# DIY_OpenEVSE_PLUS.net
KiCad netlist of a schematic drawn in EAGLE
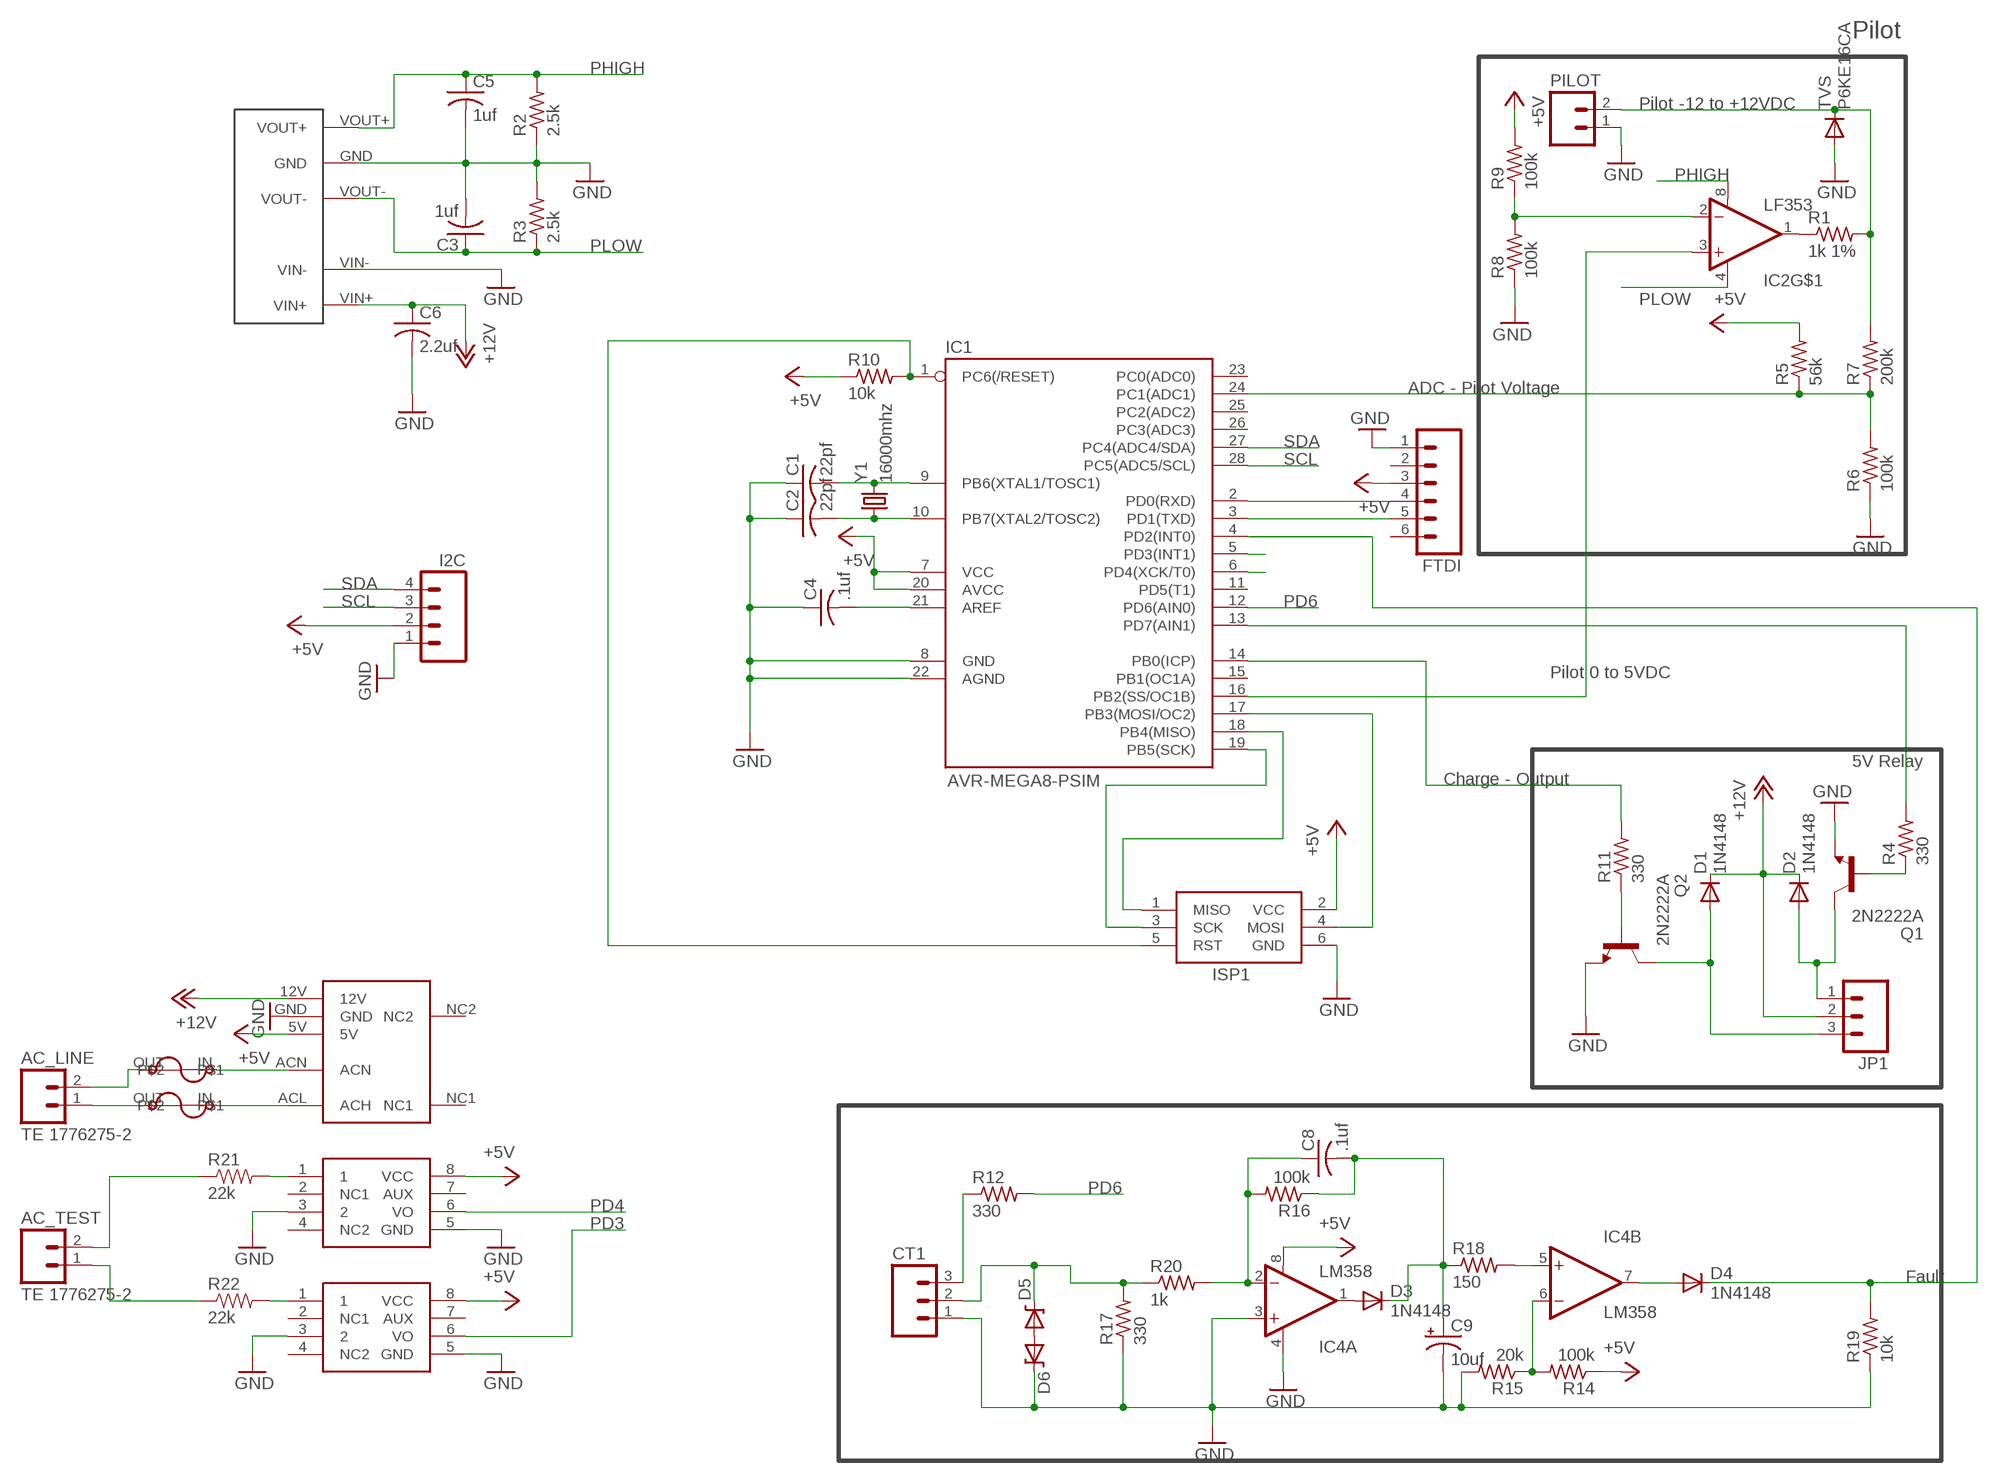
[diagram p0: schematic, sheet 1]

(export (version "E")
  (design (tool "Eeschema 10.0.6"))
  (components
    (comp (ref "AC_LINE")
      (value "TE 1776275-2")
      (footprint "eagle-import:SCREWTERMINAL-3.5MM-2_LOCK")
      (libsource (lib "eagle-import") (part "M023.5MM_LOCK"))
    )
    (comp (ref "AC_TEST")
      (value "TE 1776275-2")
      (footprint "eagle-import:SCREWTERMINAL-3.5MM-2_LOCK")
      (libsource (lib "eagle-import") (part "M023.5MM_LOCK"))
    )
    (comp (ref "C1")
      (value "22pf")
      (footprint "eagle-import:C025-024X044")
      (libsource (lib "eagle-import") (part "C-US025-024X044"))
    )
    (comp (ref "C2")
      (value "22pf")
      (footprint "eagle-import:C025-024X044")
      (libsource (lib "eagle-import") (part "C-US025-024X044"))
    )
    (comp (ref "C3")
      (value "1uf")
      (footprint "eagle-import:C025-024X044")
      (libsource (lib "eagle-import") (part "C-US025-024X044"))
    )
    (comp (ref "C4")
      (value ".1uf")
      (footprint "eagle-import:C025-024X044")
      (libsource (lib "eagle-import") (part "C-US025-024X044"))
    )
    (comp (ref "C5")
      (value "1uf")
      (footprint "eagle-import:C025-024X044")
      (libsource (lib "eagle-import") (part "C-US025-024X044"))
    )
    (comp (ref "C6")
      (value "2.2uf")
      (footprint "eagle-import:C025-024X044")
      (libsource (lib "eagle-import") (part "C-US025-024X044"))
    )
    (comp (ref "C8")
      (value ".1uf")
      (footprint "eagle-import:C025-024X044")
      (libsource (lib "eagle-import") (part "C-US025-024X044"))
    )
    (comp (ref "C9")
      (value "10uf")
      (footprint "eagle-import:CPOL-RADIAL-10UF-25V")
      (libsource (lib "eagle-import") (part "CAP_POLPTH2"))
    )
    (comp (ref "CT1")
      (value "M03LOCK")
      (footprint "eagle-import:1X03_LOCK")
      (libsource (lib "eagle-import") (part "M03LOCK"))
    )
    (comp (ref "D1")
      (value "1N4148")
      (footprint "eagle-import:DIODE-1N4148")
      (libsource (lib "eagle-import") (part "DIODE1N4148"))
    )
    (comp (ref "D2")
      (value "1N4148")
      (footprint "eagle-import:DIODE-1N4148")
      (libsource (lib "eagle-import") (part "DIODE1N4148"))
    )
    (comp (ref "D3")
      (value "1N4148")
      (footprint "eagle-import:DIODE-1N4148")
      (libsource (lib "eagle-import") (part "DIODE1N4148"))
    )
    (comp (ref "D4")
      (value "1N4148")
      (footprint "eagle-import:DIODE-1N4148")
      (libsource (lib "eagle-import") (part "DIODE1N4148"))
    )
    (comp (ref "D5")
      (value "DIODE-ZENERPTH")
      (footprint "eagle-import:DIODE-ZENER")
      (libsource (lib "eagle-import") (part "DIODE-ZENERPTH"))
    )
    (comp (ref "D6")
      (value "DIODE-ZENERPTH")
      (footprint "eagle-import:DIODE-ZENER")
      (libsource (lib "eagle-import") (part "DIODE-ZENERPTH"))
    )
    (comp (ref "DCDC")
      (value "D107E")
      (footprint "eagle-import:DCDC_SIP")
      (libsource (lib "eagle-import") (part "DCDC_SIP"))
    )
    (comp (ref "FTDI")
      (value "M06LOCK")
      (footprint "eagle-import:1X06_LOCK")
      (libsource (lib "eagle-import") (part "M06LOCK"))
    )
    (comp (ref "I2C")
      (value "M04LOCK")
      (footprint "eagle-import:1X04_LOCK")
      (libsource (lib "eagle-import") (part "M04LOCK"))
    )
    (comp (ref "IC1")
      (value "AVR-MEGA8-PSIM")
      (footprint "eagle-import:DIL28-3-SIMON")
      (libsource (lib "eagle-import") (part "AVR-MEGA8-PSIM"))
    )
    (comp (ref "IC2")
      (value "LF353")
      (footprint "eagle-import:DIP08")
      (libsource (lib "eagle-import") (part "LM358"))
    )
    (comp (ref "IC3")
      (value "MID400")
      (footprint "eagle-import:DIP08")
      (libsource (lib "eagle-import") (part "MID400"))
    )
    (comp (ref "IC4")
      (value "LM358")
      (footprint "eagle-import:DIP08")
      (libsource (lib "eagle-import") (part "OPAMP-DUALDIP"))
    )
    (comp (ref "IC5")
      (value "MID400")
      (footprint "eagle-import:DIP08")
      (libsource (lib "eagle-import") (part "MID400"))
    )
    (comp (ref "ISP1")
      (value "AVRISP-6")
      (footprint "eagle-import:AVRISP")
      (libsource (lib "eagle-import") (part "AVRISP-6"))
    )
    (comp (ref "JP1")
      (value "M03SCREW_LOCK")
      (footprint "eagle-import:SCREWTERMINAL-3.5MM-3_LOCK.007S")
      (libsource (lib "eagle-import") (part "M03SCREW_LOCK"))
    )
    (comp (ref "PILOT")
      (value "M025MM")
      (footprint "eagle-import:SCREWTERMINAL-5MM-2")
      (libsource (lib "eagle-import") (part "M025MM"))
    )
    (comp (ref "Q1")
      (value "2N2222A")
      (footprint "eagle-import:TO18")
      (libsource (lib "eagle-import") (part "2N2222A"))
    )
    (comp (ref "Q2")
      (value "2N2222A")
      (footprint "eagle-import:TO18")
      (libsource (lib "eagle-import") (part "2N2222A"))
    )
    (comp (ref "R1")
      (value "1k 1%")
      (footprint "eagle-import:0204_7")
      (libsource (lib "eagle-import") (part "R-US_0204/7"))
    )
    (comp (ref "R2")
      (value "2.5k")
      (footprint "eagle-import:0204_7")
      (libsource (lib "eagle-import") (part "R-US_0204/7"))
    )
    (comp (ref "R3")
      (value "2.5k")
      (footprint "eagle-import:0204_7")
      (libsource (lib "eagle-import") (part "R-US_0204/7"))
    )
    (comp (ref "R4")
      (value "330")
      (footprint "eagle-import:0204_7")
      (libsource (lib "eagle-import") (part "R-US_0204/7"))
    )
    (comp (ref "R5")
      (value "56k")
      (footprint "eagle-import:0204_7")
      (libsource (lib "eagle-import") (part "R-US_0204/7"))
    )
    (comp (ref "R6")
      (value "100k")
      (footprint "eagle-import:0204_7")
      (libsource (lib "eagle-import") (part "R-US_0204/7"))
    )
    (comp (ref "R7")
      (value "200k")
      (footprint "eagle-import:0204_7")
      (libsource (lib "eagle-import") (part "R-US_0204/7"))
    )
    (comp (ref "R8")
      (value "100k")
      (footprint "eagle-import:0204_7")
      (libsource (lib "eagle-import") (part "R-US_0204/7"))
    )
    (comp (ref "R9")
      (value "100k")
      (footprint "eagle-import:0204_7")
      (libsource (lib "eagle-import") (part "R-US_0204/7"))
    )
    (comp (ref "R10")
      (value "10k")
      (footprint "eagle-import:0204_7")
      (libsource (lib "eagle-import") (part "R-US_0204/7"))
    )
    (comp (ref "R11")
      (value "330")
      (footprint "eagle-import:0204_7")
      (libsource (lib "eagle-import") (part "R-US_0204/7"))
    )
    (comp (ref "R12")
      (value "330")
      (footprint "eagle-import:0204_7")
      (libsource (lib "eagle-import") (part "R-US_0204/7"))
    )
    (comp (ref "R14")
      (value "100k")
      (footprint "eagle-import:0204_7")
      (libsource (lib "eagle-import") (part "R-US_0204/7"))
    )
    (comp (ref "R15")
      (value "20k")
      (footprint "eagle-import:0204_7")
      (libsource (lib "eagle-import") (part "R-US_0204/7"))
    )
    (comp (ref "R16")
      (value "100k")
      (footprint "eagle-import:0204_7")
      (libsource (lib "eagle-import") (part "R-US_0204/7"))
    )
    (comp (ref "R17")
      (value "330")
      (footprint "eagle-import:0204_7")
      (libsource (lib "eagle-import") (part "R-US_0204/7"))
    )
    (comp (ref "R18")
      (value "150")
      (footprint "eagle-import:0204_7")
      (libsource (lib "eagle-import") (part "R-US_0204/7"))
    )
    (comp (ref "R19")
      (value "10k")
      (footprint "eagle-import:0204_7")
      (libsource (lib "eagle-import") (part "R-US_0204/7"))
    )
    (comp (ref "R20")
      (value "1k")
      (footprint "eagle-import:0204_7")
      (libsource (lib "eagle-import") (part "R-US_0204/7"))
    )
    (comp (ref "R21")
      (value "22k")
      (footprint "eagle-import:AXIAL-0.4")
      (libsource (lib "eagle-import") (part "RESISTORPTH-1/4W"))
    )
    (comp (ref "R22")
      (value "22k")
      (footprint "eagle-import:AXIAL-0.4")
      (libsource (lib "eagle-import") (part "RESISTORPTH-1/4W"))
    )
    (comp (ref "TVS")
      (value "P6KE16CA")
      (footprint "eagle-import:DIODE-1N4001")
      (libsource (lib "eagle-import") (part "DIODEPTH"))
    )
    (comp (ref "U$3")
      (value "BEL1AFUSE")
      (footprint "eagle-import:BELFUSE1A")
      (libsource (lib "eagle-import") (part "BEL1AFUSE"))
    )
    (comp (ref "U$4")
      (value "MPM-04E-1205")
      (footprint "eagle-import:MPM-04E-1205")
      (libsource (lib "eagle-import") (part "MPM-04E-1205"))
    )
    (comp (ref "U$5")
      (value "BEL1AFUSE")
      (footprint "eagle-import:BELFUSE1A")
      (libsource (lib "eagle-import") (part "BEL1AFUSE"))
    )
    (comp (ref "Y1")
      (value "16000mhz")
      (footprint "eagle-import:HC49U-V")
      (libsource (lib "eagle-import") (part "CRYSTALHC49UV"))
    )
  )
  (nets
    (net (code "1") (name "+5V") (class "Default")
      (node (ref "FTDI") (pin "3") (pinfunction "3_3") (pintype "passive"))
      (node (ref "I2C") (pin "2") (pinfunction "2_2") (pintype "passive"))
      (node (ref "IC1") (pin "20") (pinfunction "AVCC_20") (pintype "bidirectional"))
      (node (ref "IC1") (pin "7") (pinfunction "VCC_7") (pintype "bidirectional"))
      (node (ref "IC3") (pin "8") (pinfunction "VCC_8") (pintype "bidirectional"))
      (node (ref "IC4") (pin "8") (pinfunction "V+_8") (pintype "power_in"))
      (node (ref "IC5") (pin "8") (pinfunction "VCC_8") (pintype "bidirectional"))
      (node (ref "ISP1") (pin "2") (pinfunction "VCC_2") (pintype "power_in"))
      (node (ref "R10") (pin "1") (pinfunction "1_1") (pintype "passive"))
      (node (ref "R14") (pin "1") (pinfunction "1_1") (pintype "passive"))
      (node (ref "R5") (pin "2") (pinfunction "2_2") (pintype "passive"))
      (node (ref "R9") (pin "2") (pinfunction "2_2") (pintype "passive"))
      (node (ref "U$4") (pin "5V") (pinfunction "5V_5V") (pintype "bidirectional"))
    )
    (net (code "2") (name "+12V") (class "Default")
      (node (ref "C6") (pin "1") (pinfunction "1_1") (pintype "passive"))
      (node (ref "D1") (pin "C") (pinfunction "C_C") (pintype "passive"))
      (node (ref "D2") (pin "C") (pinfunction "C_C") (pintype "passive"))
      (node (ref "DCDC") (pin "VIN+") (pinfunction "VIN+_VIN+") (pintype "bidirectional"))
      (node (ref "JP1") (pin "2") (pinfunction "2_2") (pintype "passive"))
      (node (ref "U$4") (pin "12V") (pinfunction "12V_12V") (pintype "bidirectional"))
    )
    (net (code "3") (name "/PD3") (class "Default")
      (node (ref "IC1") (pin "5") (pinfunction "PD3(INT1)_5") (pintype "bidirectional"))
      (node (ref "IC5") (pin "6") (pinfunction "VO_6") (pintype "bidirectional"))
    )
    (net (code "4") (name "/PD4") (class "Default")
      (node (ref "IC1") (pin "6") (pinfunction "PD4(XCK/T0)_6") (pintype "bidirectional"))
      (node (ref "IC3") (pin "6") (pinfunction "VO_6") (pintype "bidirectional"))
    )
    (net (code "5") (name "/PD6") (class "Default")
      (node (ref "IC1") (pin "12") (pinfunction "PD6(AIN0)_12") (pintype "bidirectional"))
      (node (ref "R12") (pin "2") (pinfunction "2_2") (pintype "passive"))
    )
    (net (code "6") (name "/PHIGH") (class "Default")
      (node (ref "C5") (pin "1") (pinfunction "1_1") (pintype "passive"))
      (node (ref "DCDC") (pin "VOUT+") (pinfunction "VOUT+_VOUT+") (pintype "bidirectional"))
      (node (ref "IC2") (pin "8") (pinfunction "V+_8") (pintype "power_in"))
      (node (ref "R2") (pin "2") (pinfunction "2_2") (pintype "passive"))
    )
    (net (code "7") (name "/PLOW") (class "Default")
      (node (ref "C3") (pin "1") (pinfunction "1_1") (pintype "passive"))
      (node (ref "DCDC") (pin "VOUT-") (pinfunction "VOUT-_VOUT-") (pintype "bidirectional"))
      (node (ref "IC2") (pin "4") (pinfunction "V-_4") (pintype "power_in"))
      (node (ref "R3") (pin "1") (pinfunction "1_1") (pintype "passive"))
    )
    (net (code "8") (name "/SCL") (class "Default")
      (node (ref "I2C") (pin "3") (pinfunction "3_3") (pintype "passive"))
      (node (ref "IC1") (pin "28") (pinfunction "PC5(ADC5/SCL)_28") (pintype "bidirectional"))
    )
    (net (code "9") (name "/SDA") (class "Default")
      (node (ref "I2C") (pin "4") (pinfunction "4_4") (pintype "passive"))
      (node (ref "IC1") (pin "27") (pinfunction "PC4(ADC4/SDA)_27") (pintype "bidirectional"))
    )
    (net (code "10") (name "GND") (class "Default")
      (node (ref "C1") (pin "1") (pinfunction "1_1") (pintype "passive"))
      (node (ref "C2") (pin "1") (pinfunction "1_1") (pintype "passive"))
      (node (ref "C3") (pin "2") (pinfunction "2_2") (pintype "passive"))
      (node (ref "C4") (pin "1") (pinfunction "1_1") (pintype "passive"))
      (node (ref "C5") (pin "2") (pinfunction "2_2") (pintype "passive"))
      (node (ref "C6") (pin "2") (pinfunction "2_2") (pintype "passive"))
      (node (ref "C9") (pin "2") (pinfunction "-_2") (pintype "passive"))
      (node (ref "CT1") (pin "1") (pinfunction "1_1") (pintype "passive"))
      (node (ref "D6") (pin "P$1") (pinfunction "C_P$1") (pintype "passive"))
      (node (ref "DCDC") (pin "GND") (pinfunction "GND_GND") (pintype "bidirectional"))
      (node (ref "DCDC") (pin "VIN-") (pinfunction "VIN-_VIN-") (pintype "bidirectional"))
      (node (ref "FTDI") (pin "1") (pinfunction "1_1") (pintype "passive"))
      (node (ref "I2C") (pin "1") (pinfunction "1_1") (pintype "passive"))
      (node (ref "IC1") (pin "22") (pinfunction "AGND_22") (pintype "bidirectional"))
      (node (ref "IC1") (pin "8") (pinfunction "GND_8") (pintype "bidirectional"))
      (node (ref "IC3") (pin "3") (pinfunction "2_3") (pintype "bidirectional"))
      (node (ref "IC3") (pin "5") (pinfunction "GND_5") (pintype "bidirectional"))
      (node (ref "IC4") (pin "3") (pinfunction "+IN_3") (pintype "input"))
      (node (ref "IC4") (pin "4") (pinfunction "V-_4") (pintype "power_in"))
      (node (ref "IC5") (pin "3") (pinfunction "2_3") (pintype "bidirectional"))
      (node (ref "IC5") (pin "5") (pinfunction "GND_5") (pintype "bidirectional"))
      (node (ref "ISP1") (pin "6") (pinfunction "GND_6") (pintype "power_in"))
      (node (ref "PILOT") (pin "1") (pinfunction "1_1") (pintype "passive"))
      (node (ref "Q1") (pin "1") (pinfunction "E_1") (pintype "passive"))
      (node (ref "Q2") (pin "1") (pinfunction "E_1") (pintype "passive"))
      (node (ref "R15") (pin "2") (pinfunction "2_2") (pintype "passive"))
      (node (ref "R17") (pin "1") (pinfunction "1_1") (pintype "passive"))
      (node (ref "R19") (pin "1") (pinfunction "1_1") (pintype "passive"))
      (node (ref "R2") (pin "1") (pinfunction "1_1") (pintype "passive"))
      (node (ref "R3") (pin "2") (pinfunction "2_2") (pintype "passive"))
      (node (ref "R6") (pin "1") (pinfunction "1_1") (pintype "passive"))
      (node (ref "R8") (pin "1") (pinfunction "1_1") (pintype "passive"))
      (node (ref "TVS") (pin "A") (pinfunction "A_A") (pintype "passive"))
      (node (ref "U$4") (pin "GND") (pinfunction "GND_GND") (pintype "bidirectional"))
    )
    (net (code "11") (name "Net-(C9-+)") (class "Default")
      (node (ref "C8") (pin "2") (pinfunction "2_2") (pintype "passive"))
      (node (ref "C9") (pin "1") (pinfunction "+_1") (pintype "passive"))
      (node (ref "D3") (pin "C") (pinfunction "C_C") (pintype "passive"))
      (node (ref "R16") (pin "1") (pinfunction "1_1") (pintype "passive"))
      (node (ref "R18") (pin "1") (pinfunction "1_1") (pintype "passive"))
    )
    (net (code "12") (name "Net-(CT1-Pad3)") (class "Default")
      (node (ref "CT1") (pin "3") (pinfunction "3_3") (pintype "passive"))
      (node (ref "R12") (pin "1") (pinfunction "1_1") (pintype "passive"))
    )
    (net (code "13") (name "Net-(D5-A)") (class "Default")
      (node (ref "D5") (pin "P$2") (pinfunction "A_P$2") (pintype "passive"))
      (node (ref "D6") (pin "P$2") (pinfunction "A_P$2") (pintype "passive"))
    )
    (net (code "14") (name "Net-(D5-C)") (class "Default")
      (node (ref "CT1") (pin "2") (pinfunction "2_2") (pintype "passive"))
      (node (ref "D5") (pin "P$1") (pinfunction "C_P$1") (pintype "passive"))
      (node (ref "R17") (pin "2") (pinfunction "2_2") (pintype "passive"))
      (node (ref "R20") (pin "1") (pinfunction "1_1") (pintype "passive"))
    )
    (net (code "15") (name "Net-(IC1-AREF)") (class "Default")
      (node (ref "C4") (pin "2") (pinfunction "2_2") (pintype "passive"))
      (node (ref "IC1") (pin "21") (pinfunction "AREF_21") (pintype "bidirectional"))
    )
    (net (code "16") (name "Net-(IC1-PB0(ICP))") (class "Default")
      (node (ref "IC1") (pin "14") (pinfunction "PB0(ICP)_14") (pintype "bidirectional"))
      (node (ref "R11") (pin "2") (pinfunction "2_2") (pintype "passive"))
    )
    (net (code "17") (name "Net-(IC1-PB2(SS{slash}OC1B))") (class "Default")
      (node (ref "IC1") (pin "16") (pinfunction "PB2(SS/OC1B)_16") (pintype "bidirectional"))
      (node (ref "IC2") (pin "3") (pinfunction "+IN_3") (pintype "input"))
    )
    (net (code "18") (name "Net-(IC1-PB3(MOSI{slash}OC2))") (class "Default")
      (node (ref "IC1") (pin "17") (pinfunction "PB3(MOSI/OC2)_17") (pintype "bidirectional"))
      (node (ref "ISP1") (pin "4") (pinfunction "MOSI_4") (pintype "output"))
    )
    (net (code "19") (name "Net-(IC1-PB4(MISO))") (class "Default")
      (node (ref "IC1") (pin "18") (pinfunction "PB4(MISO)_18") (pintype "bidirectional"))
      (node (ref "ISP1") (pin "1") (pinfunction "MISO_1") (pintype "input"))
    )
    (net (code "20") (name "Net-(IC1-PB5(SCK))") (class "Default")
      (node (ref "IC1") (pin "19") (pinfunction "PB5(SCK)_19") (pintype "bidirectional"))
      (node (ref "ISP1") (pin "3") (pinfunction "SCK_3") (pintype "output"))
    )
    (net (code "21") (name "Net-(IC1-PB6(XTAL1{slash}TOSC1))") (class "Default")
      (node (ref "C1") (pin "2") (pinfunction "2_2") (pintype "passive"))
      (node (ref "IC1") (pin "9") (pinfunction "PB6(XTAL1/TOSC1)_9") (pintype "bidirectional"))
      (node (ref "Y1") (pin "2") (pinfunction "2_2") (pintype "passive"))
    )
    (net (code "22") (name "Net-(IC1-PB7(XTAL2{slash}TOSC2))") (class "Default")
      (node (ref "C2") (pin "2") (pinfunction "2_2") (pintype "passive"))
      (node (ref "IC1") (pin "10") (pinfunction "PB7(XTAL2/TOSC2)_10") (pintype "bidirectional"))
      (node (ref "Y1") (pin "1") (pinfunction "1_1") (pintype "passive"))
    )
    (net (code "23") (name "Net-(IC1-PC1(ADC1))") (class "Default")
      (node (ref "IC1") (pin "24") (pinfunction "PC1(ADC1)_24") (pintype "bidirectional"))
      (node (ref "R5") (pin "1") (pinfunction "1_1") (pintype "passive"))
      (node (ref "R6") (pin "2") (pinfunction "2_2") (pintype "passive"))
      (node (ref "R7") (pin "1") (pinfunction "1_1") (pintype "passive"))
    )
    (net (code "24") (name "Net-(IC1-PC6({slash}RESET))") (class "Default")
      (node (ref "IC1") (pin "1") (pinfunction "PC6(/RESET)_1") (pintype "bidirectional"))
      (node (ref "ISP1") (pin "5") (pinfunction "RST_5") (pintype "output"))
      (node (ref "R10") (pin "2") (pinfunction "2_2") (pintype "passive"))
    )
    (net (code "25") (name "Net-(IC1-PD0(RXD))") (class "Default")
      (node (ref "FTDI") (pin "4") (pinfunction "4_4") (pintype "passive"))
      (node (ref "IC1") (pin "2") (pinfunction "PD0(RXD)_2") (pintype "bidirectional"))
    )
    (net (code "26") (name "Net-(IC1-PD1(TXD))") (class "Default")
      (node (ref "FTDI") (pin "5") (pinfunction "5_5") (pintype "passive"))
      (node (ref "IC1") (pin "3") (pinfunction "PD1(TXD)_3") (pintype "bidirectional"))
    )
    (net (code "27") (name "Net-(IC1-PD2(INT0))") (class "Default")
      (node (ref "D4") (pin "C") (pinfunction "C_C") (pintype "passive"))
      (node (ref "IC1") (pin "4") (pinfunction "PD2(INT0)_4") (pintype "bidirectional"))
      (node (ref "R19") (pin "2") (pinfunction "2_2") (pintype "passive"))
    )
    (net (code "28") (name "Net-(IC1-PD7(AIN1))") (class "Default")
      (node (ref "IC1") (pin "13") (pinfunction "PD7(AIN1)_13") (pintype "bidirectional"))
      (node (ref "R4") (pin "2") (pinfunction "2_2") (pintype "passive"))
    )
    (net (code "29") (name "Net-(IC2A--IN)") (class "Default")
      (node (ref "IC2") (pin "2") (pinfunction "-IN_2") (pintype "input"))
      (node (ref "R8") (pin "2") (pinfunction "2_2") (pintype "passive"))
      (node (ref "R9") (pin "1") (pinfunction "1_1") (pintype "passive"))
    )
    (net (code "30") (name "Net-(IC2A-OUT)") (class "Default")
      (node (ref "IC2") (pin "1") (pinfunction "OUT_1") (pintype "output"))
      (node (ref "R1") (pin "1") (pinfunction "1_1") (pintype "passive"))
    )
    (net (code "31") (name "Net-(IC4A--IN)") (class "Default")
      (node (ref "C8") (pin "1") (pinfunction "1_1") (pintype "passive"))
      (node (ref "IC4") (pin "2") (pinfunction "-IN_2") (pintype "input"))
      (node (ref "R16") (pin "2") (pinfunction "2_2") (pintype "passive"))
      (node (ref "R20") (pin "2") (pinfunction "2_2") (pintype "passive"))
    )
    (net (code "32") (name "Net-(IC4A-OUT)") (class "Default")
      (node (ref "D3") (pin "A") (pinfunction "A_A") (pintype "passive"))
      (node (ref "IC4") (pin "1") (pinfunction "OUT_1") (pintype "output"))
    )
    (net (code "33") (name "Net-(IC4B-+IN)") (class "Default")
      (node (ref "IC4") (pin "5") (pinfunction "+IN_5") (pintype "input"))
      (node (ref "R18") (pin "2") (pinfunction "2_2") (pintype "passive"))
    )
    (net (code "34") (name "Net-(IC4B--IN)") (class "Default")
      (node (ref "IC4") (pin "6") (pinfunction "-IN_6") (pintype "input"))
      (node (ref "R14") (pin "2") (pinfunction "2_2") (pintype "passive"))
      (node (ref "R15") (pin "1") (pinfunction "1_1") (pintype "passive"))
    )
    (net (code "35") (name "Net-(IC4B-OUT)") (class "Default")
      (node (ref "D4") (pin "A") (pinfunction "A_A") (pintype "passive"))
      (node (ref "IC4") (pin "7") (pinfunction "OUT_7") (pintype "output"))
    )
    (net (code "36") (name "Net-(PILOT-Pad2)") (class "Default")
      (node (ref "PILOT") (pin "2") (pinfunction "2_2") (pintype "passive"))
      (node (ref "R1") (pin "2") (pinfunction "2_2") (pintype "passive"))
      (node (ref "R7") (pin "2") (pinfunction "2_2") (pintype "passive"))
      (node (ref "TVS") (pin "C") (pinfunction "C_C") (pintype "passive"))
    )
    (net (code "37") (name "Net-(Q1-B)") (class "Default")
      (node (ref "Q1") (pin "2") (pinfunction "B_2") (pintype "passive"))
      (node (ref "R4") (pin "1") (pinfunction "1_1") (pintype "passive"))
    )
    (net (code "38") (name "Net-(Q1-C)") (class "Default")
      (node (ref "D2") (pin "A") (pinfunction "A_A") (pintype "passive"))
      (node (ref "JP1") (pin "1") (pinfunction "1_1") (pintype "passive"))
      (node (ref "Q1") (pin "3") (pinfunction "C_3") (pintype "passive"))
    )
    (net (code "39") (name "Net-(Q2-B)") (class "Default")
      (node (ref "Q2") (pin "2") (pinfunction "B_2") (pintype "passive"))
      (node (ref "R11") (pin "1") (pinfunction "1_1") (pintype "passive"))
    )
    (net (code "40") (name "Net-(Q2-C)") (class "Default")
      (node (ref "D1") (pin "A") (pinfunction "A_A") (pintype "passive"))
      (node (ref "JP1") (pin "3") (pinfunction "3_3") (pintype "passive"))
      (node (ref "Q2") (pin "3") (pinfunction "C_3") (pintype "passive"))
    )
    (net (code "41") (name "Net-(R21-1)") (class "Default")
      (node (ref "AC_TEST") (pin "2") (pinfunction "2_2") (pintype "passive"))
      (node (ref "R21") (pin "P$1") (pinfunction "1_P$1") (pintype "passive"))
    )
    (net (code "42") (name "Net-(R21-2)") (class "Default")
      (node (ref "IC3") (pin "1") (pinfunction "1_1") (pintype "bidirectional"))
      (node (ref "R21") (pin "P$2") (pinfunction "2_P$2") (pintype "passive"))
    )
    (net (code "43") (name "Net-(R22-1)") (class "Default")
      (node (ref "AC_TEST") (pin "1") (pinfunction "1_1") (pintype "passive"))
      (node (ref "R22") (pin "P$1") (pinfunction "1_P$1") (pintype "passive"))
    )
    (net (code "44") (name "Net-(R22-2)") (class "Default")
      (node (ref "IC5") (pin "1") (pinfunction "1_1") (pintype "bidirectional"))
      (node (ref "R22") (pin "P$2") (pinfunction "2_P$2") (pintype "passive"))
    )
    (net (code "45") (name "Net-(U$3-P$1)") (class "Default")
      (node (ref "AC_LINE") (pin "1") (pinfunction "1_1") (pintype "passive"))
      (node (ref "U$3") (pin "OUT") (pinfunction "P$1_OUT") (pintype "bidirectional"))
    )
    (net (code "46") (name "Net-(U$3-P$2)") (class "Default")
      (node (ref "U$3") (pin "IN") (pinfunction "P$2_IN") (pintype "bidirectional"))
      (node (ref "U$4") (pin "ACL") (pinfunction "ACH_ACL") (pintype "bidirectional"))
    )
    (net (code "47") (name "Net-(U$5-P$1)") (class "Default")
      (node (ref "AC_LINE") (pin "2") (pinfunction "2_2") (pintype "passive"))
      (node (ref "U$5") (pin "OUT") (pinfunction "P$1_OUT") (pintype "bidirectional"))
    )
    (net (code "48") (name "Net-(U$5-P$2)") (class "Default")
      (node (ref "U$4") (pin "ACN") (pinfunction "ACN_ACN") (pintype "bidirectional"))
      (node (ref "U$5") (pin "IN") (pinfunction "P$2_IN") (pintype "bidirectional"))
    )
    (net (code "49") (name "unconnected-(FTDI-Pad2)") (class "Default")
      (node (ref "FTDI") (pin "2") (pinfunction "2_2") (pintype "passive"))
    )
    (net (code "50") (name "unconnected-(FTDI-Pad6)") (class "Default")
      (node (ref "FTDI") (pin "6") (pinfunction "6_6") (pintype "passive"))
    )
    (net (code "51") (name "unconnected-(IC1-PB1(OC1A)-Pad15)") (class "Default")
      (node (ref "IC1") (pin "15") (pinfunction "PB1(OC1A)_15") (pintype "bidirectional"))
    )
    (net (code "52") (name "unconnected-(IC1-PC0(ADC0)-Pad23)") (class "Default")
      (node (ref "IC1") (pin "23") (pinfunction "PC0(ADC0)_23") (pintype "bidirectional"))
    )
    (net (code "53") (name "unconnected-(IC1-PC2(ADC2)-Pad25)") (class "Default")
      (node (ref "IC1") (pin "25") (pinfunction "PC2(ADC2)_25") (pintype "bidirectional"))
    )
    (net (code "54") (name "unconnected-(IC1-PC3(ADC3)-Pad26)") (class "Default")
      (node (ref "IC1") (pin "26") (pinfunction "PC3(ADC3)_26") (pintype "bidirectional"))
    )
    (net (code "55") (name "unconnected-(IC1-PD5(T1)-Pad11)") (class "Default")
      (node (ref "IC1") (pin "11") (pinfunction "PD5(T1)_11") (pintype "bidirectional"))
    )
    (net (code "56") (name "unconnected-(IC3-AUX-Pad7)") (class "Default")
      (node (ref "IC3") (pin "7") (pinfunction "AUX_7") (pintype "bidirectional"))
    )
    (net (code "57") (name "unconnected-(IC3-NC1-Pad2)") (class "Default")
      (node (ref "IC3") (pin "2") (pinfunction "NC1_2") (pintype "bidirectional"))
    )
    (net (code "58") (name "unconnected-(IC3-NC2-Pad4)") (class "Default")
      (node (ref "IC3") (pin "4") (pinfunction "NC2_4") (pintype "bidirectional"))
    )
    (net (code "59") (name "unconnected-(IC5-AUX-Pad7)") (class "Default")
      (node (ref "IC5") (pin "7") (pinfunction "AUX_7") (pintype "bidirectional"))
    )
    (net (code "60") (name "unconnected-(IC5-NC1-Pad2)") (class "Default")
      (node (ref "IC5") (pin "2") (pinfunction "NC1_2") (pintype "bidirectional"))
    )
    (net (code "61") (name "unconnected-(IC5-NC2-Pad4)") (class "Default")
      (node (ref "IC5") (pin "4") (pinfunction "NC2_4") (pintype "bidirectional"))
    )
    (net (code "62") (name "unconnected-(U$4-PadNC1)") (class "Default")
      (node (ref "U$4") (pin "NC1") (pinfunction "NC1_NC1") (pintype "bidirectional"))
    )
    (net (code "63") (name "unconnected-(U$4-PadNC2)") (class "Default")
      (node (ref "U$4") (pin "NC2") (pinfunction "NC2_NC2") (pintype "bidirectional"))
    )
  )
)
